# gloves.net
KiCad netlist of a schematic drawn in EAGLE
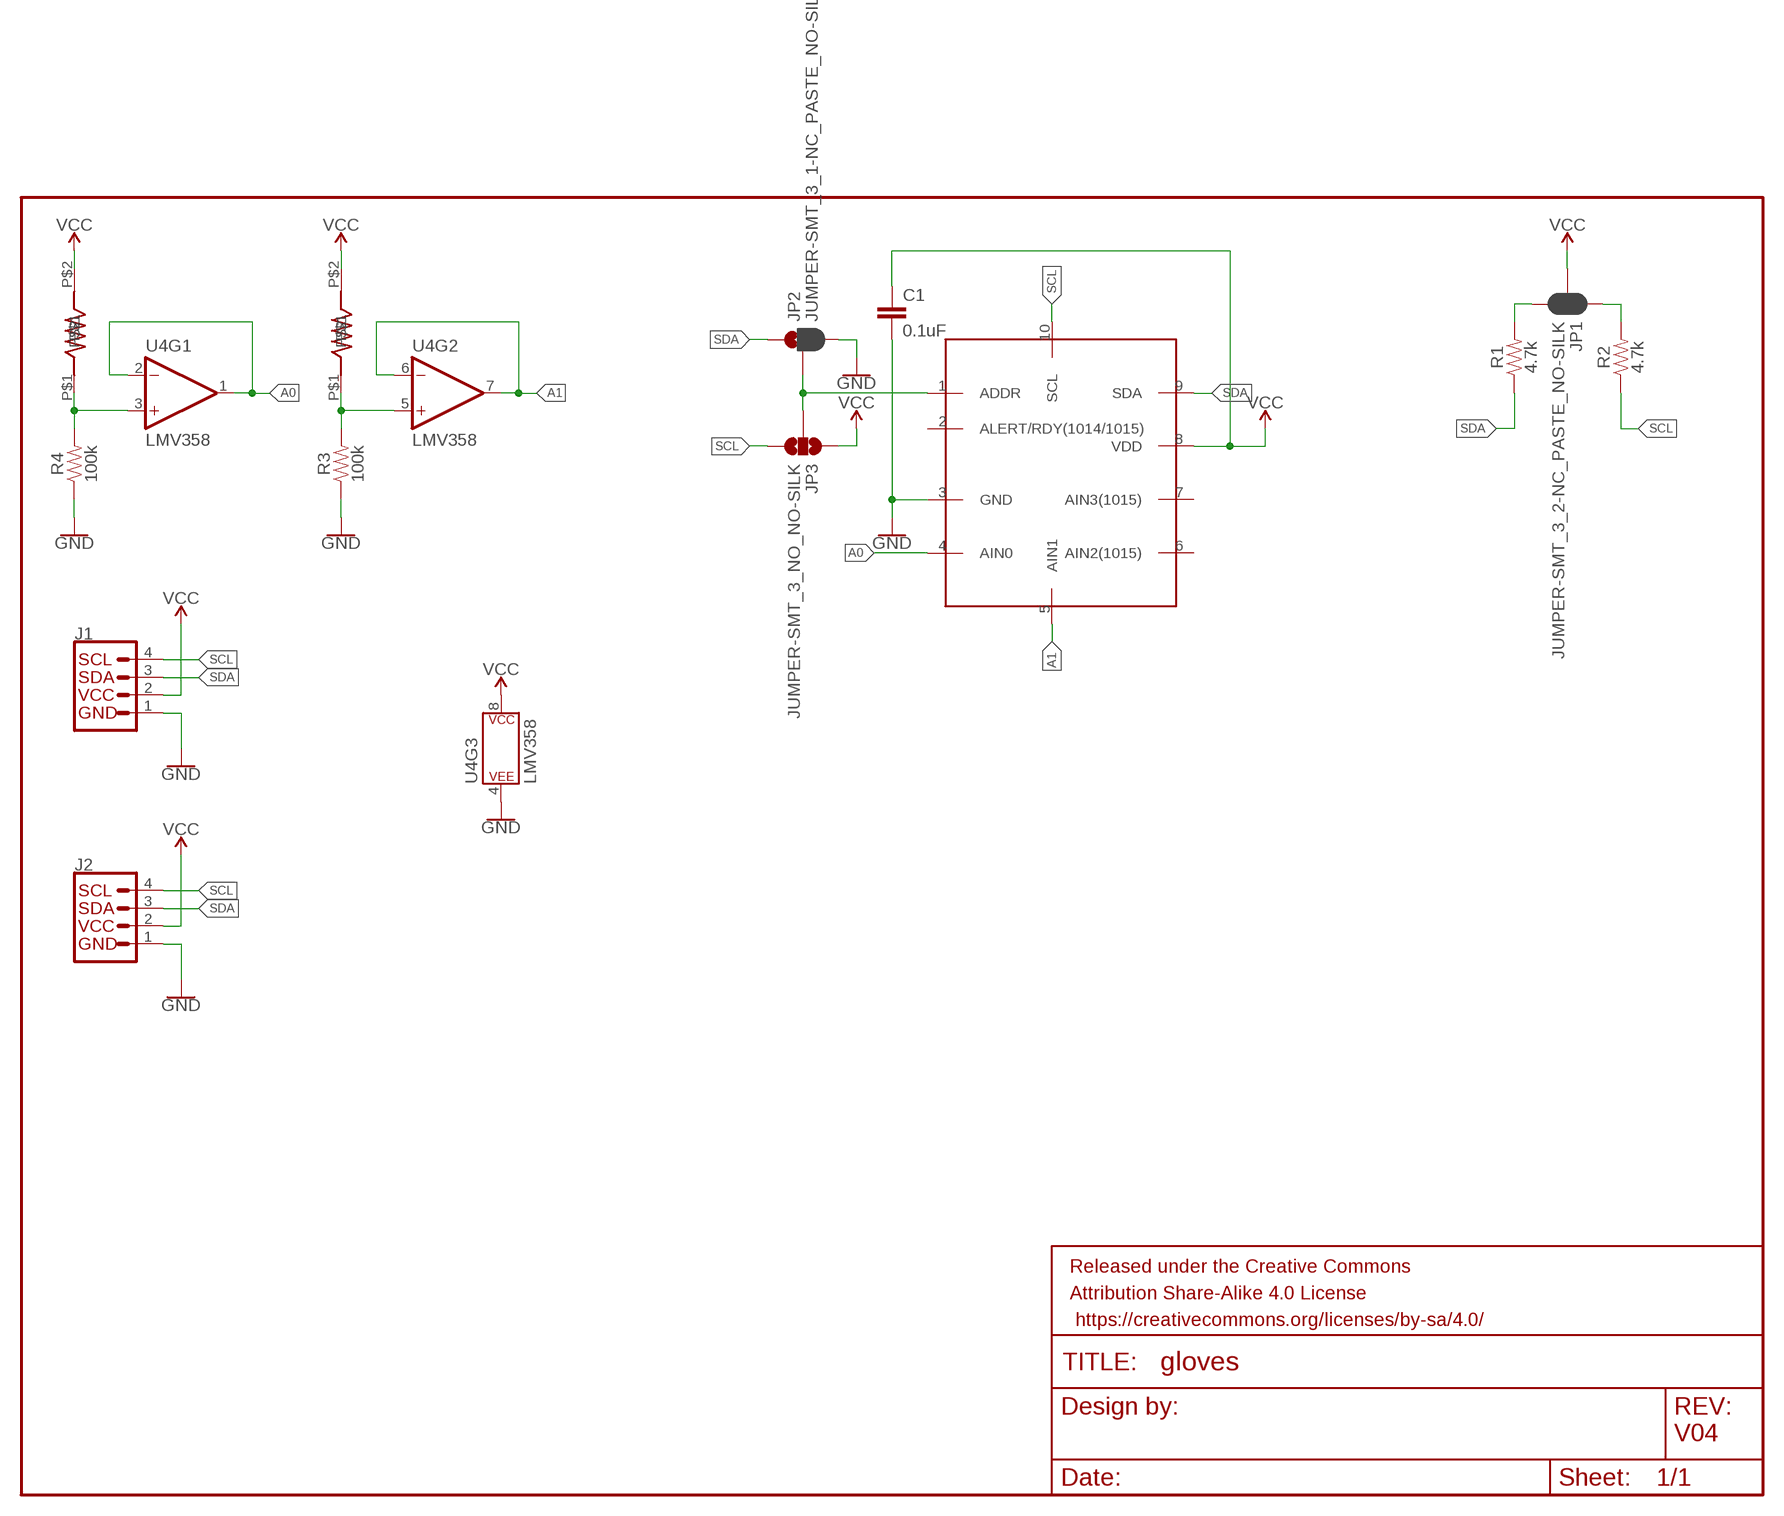
[diagram p0: schematic, sheet 1]

(export (version "E")
  (design (tool "Eeschema 10.0.6"))
  (components
    (comp (ref "C1")
      (value "0.1uF")
      (footprint "eagle-import:0603")
      (libsource (lib "eagle-import") (part "0.1UF-0603-25V-(+80/-20%)"))
    )
    (comp (ref "FRAME1")
      (value "FRAME-LETTER")
      (footprint "eagle-import:CREATIVE_COMMONS")
      (libsource (lib "eagle-import") (part "FRAME-LETTER"))
    )
    (comp (ref "J1")
      (value "QWIIC_CONNECTORJS-1MM")
      (footprint "eagle-import:1X04_1MM_RA")
      (libsource (lib "eagle-import") (part "QWIIC_CONNECTORJS-1MM"))
    )
    (comp (ref "J2")
      (value "QWIIC_CONNECTORJS-1MM")
      (footprint "eagle-import:1X04_1MM_RA")
      (libsource (lib "eagle-import") (part "QWIIC_CONNECTORJS-1MM"))
    )
    (comp (ref "JP1")
      (value "JUMPER-SMT_3_2-NC_PASTE_NO-SILK")
      (footprint "eagle-import:SMT-JUMPER_3_2-NC_PASTE_NO-SILK")
      (libsource (lib "eagle-import") (part "JUMPER-SMT_3_2-NC_PASTE_NO-SILK"))
    )
    (comp (ref "JP2")
      (value "JUMPER-SMT_3_1-NC_PASTE_NO-SILK")
      (footprint "eagle-import:SMT-JUMPER_3_1-NC_PASTE_NO-SILK")
      (libsource (lib "eagle-import") (part "JUMPER-SMT_3_1-NC_PASTE_NO-SILK"))
    )
    (comp (ref "JP3")
      (value "JUMPER-SMT_3_NO_NO-SILK")
      (footprint "eagle-import:SMT-JUMPER_3_NO_NO-SILK")
      (libsource (lib "eagle-import") (part "JUMPER-SMT_3_NO_NO-SILK"))
    )
    (comp (ref "R1")
      (value "4.7k")
      (footprint "eagle-import:0603")
      (libsource (lib "eagle-import") (part "4.7KOHM-0603-1/10W-1%"))
    )
    (comp (ref "R2")
      (value "4.7k")
      (footprint "eagle-import:0603")
      (libsource (lib "eagle-import") (part "4.7KOHM-0603-1/10W-1%"))
    )
    (comp (ref "R3")
      (value "100k")
      (footprint "eagle-import:0603")
      (libsource (lib "eagle-import") (part "100KOHM-0603-1/10W-1%"))
    )
    (comp (ref "R4")
      (value "100k")
      (footprint "eagle-import:0603")
      (libsource (lib "eagle-import") (part "100KOHM-0603-1/10W-1%"))
    )
    (comp (ref "U$1")
      (value "ADS101X-ADC_TO_I2CADS101X")
      (footprint "eagle-import:MSOP-10-GNDPAD")
      (libsource (lib "eagle-import") (part "ADS101X-ADC_TO_I2CADS101X"))
    )
    (comp (ref "U$3")
      (value "FLEX_SENSOR")
      (footprint "eagle-import:FLEX_SENSOR")
      (libsource (lib "eagle-import") (part "FLEX_SENSOR"))
    )
    (comp (ref "U$4")
      (value "FLEX_SENSOR")
      (footprint "eagle-import:FLEX_SENSOR")
      (libsource (lib "eagle-import") (part "FLEX_SENSOR"))
    )
    (comp (ref "U4")
      (value "LMV358")
      (footprint "eagle-import:SO08")
      (libsource (lib "eagle-import") (part "LMV358SOIC"))
    )
  )
  (nets
    (net (code "1") (name "A0") (class "Default")
      (node (ref "U$1") (pin "4") (pinfunction "AIN0_4") (pintype "bidirectional"))
      (node (ref "U4") (pin "1") (pinfunction "OUT_1") (pintype "output"))
      (node (ref "U4") (pin "2") (pinfunction "-IN_2") (pintype "input"))
    )
    (net (code "2") (name "A1") (class "Default")
      (node (ref "U$1") (pin "5") (pinfunction "AIN1_5") (pintype "bidirectional"))
      (node (ref "U4") (pin "6") (pinfunction "-IN_6") (pintype "input"))
      (node (ref "U4") (pin "7") (pinfunction "OUT_7") (pintype "output"))
    )
    (net (code "3") (name "GND") (class "Default")
      (node (ref "C1") (pin "2") (pinfunction "2_2") (pintype "passive"))
      (node (ref "J1") (pin "1") (pinfunction "1_1") (pintype "power_in"))
      (node (ref "J2") (pin "1") (pinfunction "1_1") (pintype "power_in"))
      (node (ref "JP2") (pin "3") (pinfunction "3_3") (pintype "passive"))
      (node (ref "R3") (pin "1") (pinfunction "1_1") (pintype "passive"))
      (node (ref "R4") (pin "1") (pinfunction "1_1") (pintype "passive"))
      (node (ref "U$1") (pin "3") (pinfunction "GND_3") (pintype "bidirectional"))
      (node (ref "U4") (pin "4") (pinfunction "P$V-_4") (pintype "bidirectional"))
    )
    (net (code "4") (name "Net-(JP1-Pad1)") (class "Default")
      (node (ref "JP1") (pin "1") (pinfunction "1_1") (pintype "passive"))
      (node (ref "R2") (pin "2") (pinfunction "2_2") (pintype "passive"))
    )
    (net (code "5") (name "Net-(JP1-Pad3)") (class "Default")
      (node (ref "JP1") (pin "3") (pinfunction "3_3") (pintype "passive"))
      (node (ref "R1") (pin "2") (pinfunction "2_2") (pintype "passive"))
    )
    (net (code "6") (name "Net-(U$1-ADDR)") (class "Default")
      (node (ref "JP2") (pin "2") (pinfunction "2_2") (pintype "passive"))
      (node (ref "JP3") (pin "2") (pinfunction "2_2") (pintype "passive"))
      (node (ref "U$1") (pin "1") (pinfunction "ADDR_1") (pintype "bidirectional"))
    )
    (net (code "7") (name "Net-(U4A-+IN)") (class "Default")
      (node (ref "R4") (pin "2") (pinfunction "2_2") (pintype "passive"))
      (node (ref "U$4") (pin "P$1") (pinfunction "P$1_P$1") (pintype "bidirectional"))
      (node (ref "U4") (pin "3") (pinfunction "+IN_3") (pintype "input"))
    )
    (net (code "8") (name "Net-(U4B-+IN)") (class "Default")
      (node (ref "R3") (pin "2") (pinfunction "2_2") (pintype "passive"))
      (node (ref "U$3") (pin "P$1") (pinfunction "P$1_P$1") (pintype "bidirectional"))
      (node (ref "U4") (pin "5") (pinfunction "+IN_5") (pintype "input"))
    )
    (net (code "9") (name "SCL") (class "Default")
      (node (ref "J1") (pin "4") (pinfunction "4_4") (pintype "passive"))
      (node (ref "J2") (pin "4") (pinfunction "4_4") (pintype "passive"))
      (node (ref "JP3") (pin "3") (pinfunction "3_3") (pintype "passive"))
      (node (ref "R2") (pin "1") (pinfunction "1_1") (pintype "passive"))
      (node (ref "U$1") (pin "10") (pinfunction "SCL_10") (pintype "bidirectional"))
    )
    (net (code "10") (name "SDA") (class "Default")
      (node (ref "J1") (pin "3") (pinfunction "3_3") (pintype "passive"))
      (node (ref "J2") (pin "3") (pinfunction "3_3") (pintype "passive"))
      (node (ref "JP2") (pin "1") (pinfunction "1_1") (pintype "passive"))
      (node (ref "R1") (pin "1") (pinfunction "1_1") (pintype "passive"))
      (node (ref "U$1") (pin "9") (pinfunction "SDA_9") (pintype "bidirectional"))
    )
    (net (code "11") (name "VCC") (class "Default")
      (node (ref "C1") (pin "1") (pinfunction "1_1") (pintype "passive"))
      (node (ref "J1") (pin "2") (pinfunction "2_2") (pintype "power_in"))
      (node (ref "J2") (pin "2") (pinfunction "2_2") (pintype "power_in"))
      (node (ref "JP1") (pin "2") (pinfunction "2_2") (pintype "passive"))
      (node (ref "JP3") (pin "1") (pinfunction "1_1") (pintype "passive"))
      (node (ref "U$1") (pin "8") (pinfunction "VDD_8") (pintype "bidirectional"))
      (node (ref "U$3") (pin "P$2") (pinfunction "P$2_P$2") (pintype "bidirectional"))
      (node (ref "U$4") (pin "P$2") (pinfunction "P$2_P$2") (pintype "bidirectional"))
      (node (ref "U4") (pin "8") (pinfunction "P$V+_8") (pintype "bidirectional"))
    )
    (net (code "12") (name "unconnected-(U$1-AIN2(1015)-Pad6)") (class "Default")
      (node (ref "U$1") (pin "6") (pinfunction "AIN2(1015)_6") (pintype "bidirectional"))
    )
    (net (code "13") (name "unconnected-(U$1-AIN3(1015)-Pad7)") (class "Default")
      (node (ref "U$1") (pin "7") (pinfunction "AIN3(1015)_7") (pintype "bidirectional"))
    )
    (net (code "14") (name "unconnected-(U$1-ALERT{slash}RDY(1014{slash}1015)-Pad2)") (class "Default")
      (node (ref "U$1") (pin "2") (pinfunction "ALERT/RDY(1014/1015)_2") (pintype "bidirectional"))
    )
  )
)
